# PROC010B_HD_Connector.net
KiCad netlist of a schematic drawn in Altium Designer
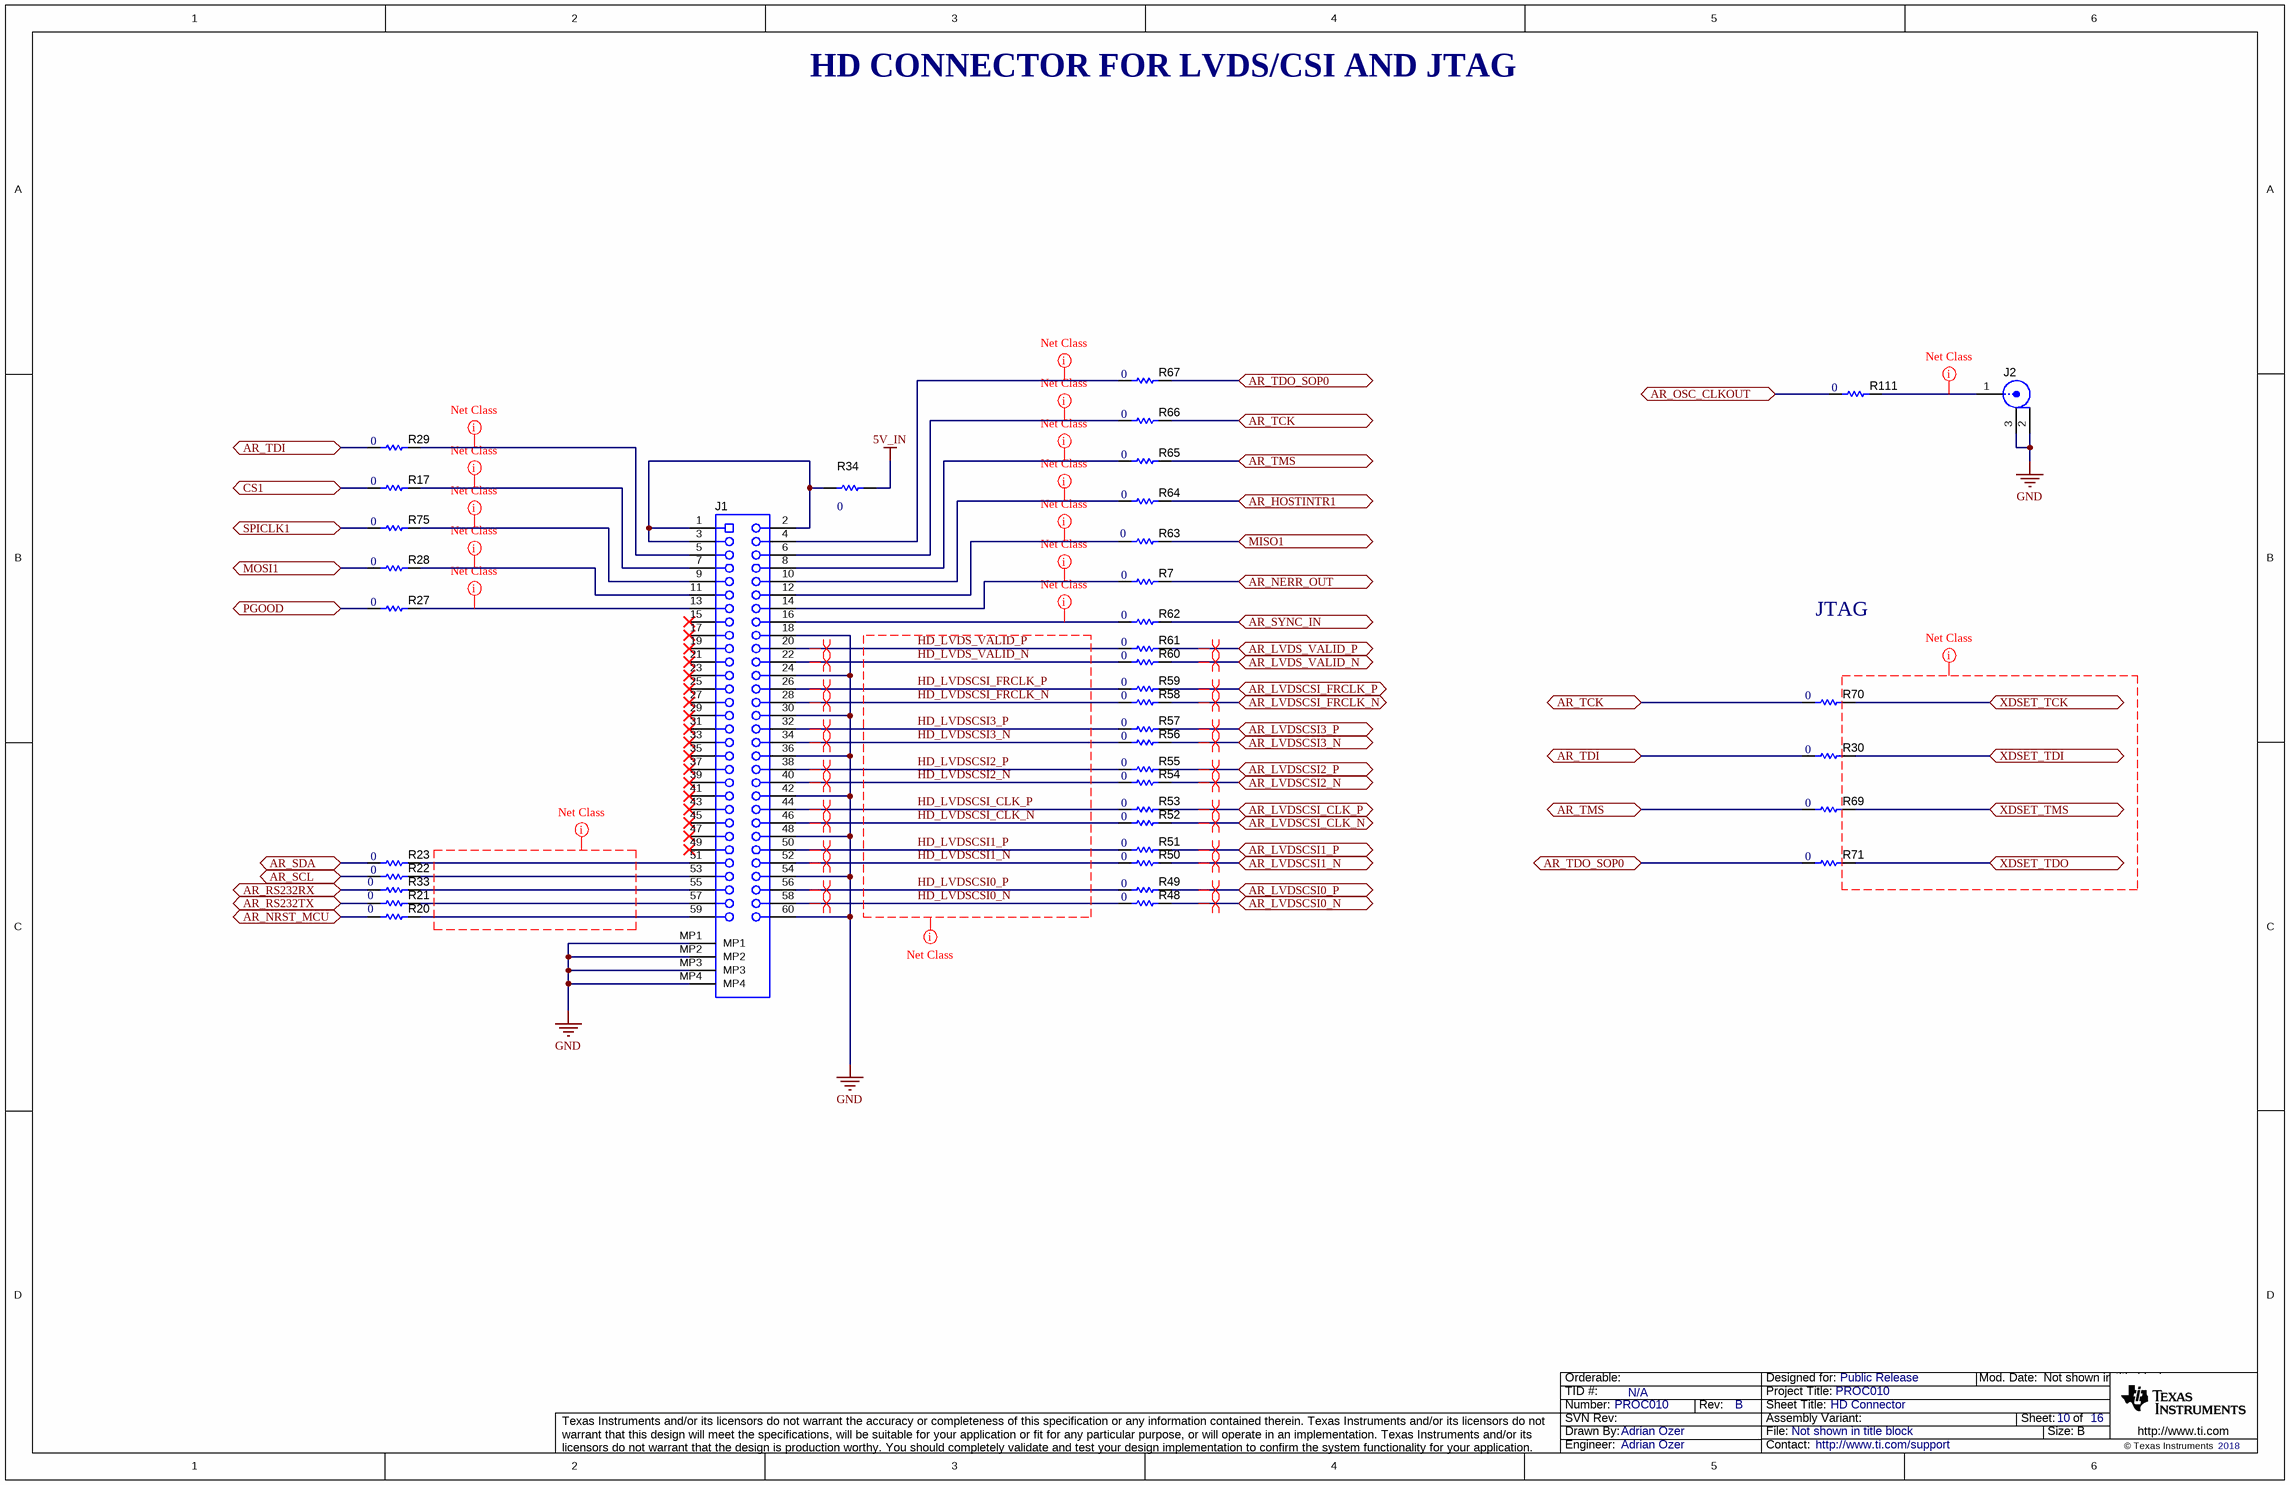
[diagram p0: PROC010B_HD Connector.SchDoc]

(export (version "E")
  (design (tool "Eeschema 10.0.6"))
  (components
    (comp (ref "J1")
      (value "QSH-030-01-L-D-A")
      (footprint "Samtec_QSH-030-01-X-D-A")
      (description "Receptacle, 0.5 mm, 30x2, Gold, TH")
      (fields (field (name "MANUFACTURER") "Samtec") (field (name "PUBLISHER") "Texas Instruments"))
      (libsource (lib "Altium Vault - TI") (part "Receptacle_30x2_4MP_LeftRight"))
    )
    (comp (ref "J2")
      (value "128-0711-201")
      (footprint "Johnson_128-0711-201")
      (description "UMC Straight Jack Receptacle, 50 Ohm, Gold, SMT")
      (fields
        (field (name "MANUFACTURER") "Cinch Connectivity")
        (field (name "PUBLISHER") "Texas Instruments")
      )
      (libsource (lib "Altium Vault - TI") (part "CMP-0055788-1"))
    )
    (comp (ref "R7")
      (value "CRCW02010000Z0ED")
      (footprint "0201_Silk")
      (description "RES, 0, 5%, 0.05 W, 0201")
      (fields (field (name "MANUFACTURER") "Vishay-Dale") (field (name "VALUEDISPLAYED") "0"))
      (libsource (lib "Altium Vault - TI") (part "Resistor"))
    )
    (comp (ref "R17")
      (value "CRCW02010000Z0ED")
      (footprint "0201_Silk")
      (description "RES, 0, 5%, 0.05 W, 0201")
      (fields (field (name "MANUFACTURER") "Vishay-Dale") (field (name "VALUEDISPLAYED") "0"))
      (libsource (lib "Altium Vault - TI") (part "Resistor"))
    )
    (comp (ref "R20")
      (value "CRCW02010000Z0ED")
      (footprint "0201_Silk")
      (description "RES, 0, 5%, 0.05 W, 0201")
      (fields (field (name "MANUFACTURER") "Vishay-Dale") (field (name "VALUEDISPLAYED") "0"))
      (libsource (lib "Altium Vault - TI") (part "Resistor"))
    )
    (comp (ref "R21")
      (value "CRCW02010000Z0ED")
      (footprint "0201_Silk")
      (description "RES, 0, 5%, 0.05 W, 0201")
      (fields (field (name "MANUFACTURER") "Vishay-Dale") (field (name "VALUEDISPLAYED") "0"))
      (libsource (lib "Altium Vault - TI") (part "Resistor"))
    )
    (comp (ref "R22")
      (value "CRCW02010000Z0ED")
      (footprint "0201_Silk")
      (description "RES, 0, 5%, 0.05 W, 0201")
      (fields (field (name "MANUFACTURER") "Vishay-Dale") (field (name "VALUEDISPLAYED") "0"))
      (libsource (lib "Altium Vault - TI") (part "Resistor"))
    )
    (comp (ref "R23")
      (value "CRCW02010000Z0ED")
      (footprint "0201_Silk")
      (description "RES, 0, 5%, 0.05 W, 0201")
      (fields (field (name "MANUFACTURER") "Vishay-Dale") (field (name "VALUEDISPLAYED") "0"))
      (libsource (lib "Altium Vault - TI") (part "Resistor"))
    )
    (comp (ref "R27")
      (value "CRCW02010000Z0ED")
      (footprint "0201_Silk")
      (description "RES, 0, 5%, 0.05 W, 0201")
      (fields (field (name "MANUFACTURER") "Vishay-Dale") (field (name "VALUEDISPLAYED") "0"))
      (libsource (lib "Altium Vault - TI") (part "Resistor"))
    )
    (comp (ref "R28")
      (value "CRCW02010000Z0ED")
      (footprint "0201_Silk")
      (description "RES, 0, 5%, 0.05 W, 0201")
      (fields (field (name "MANUFACTURER") "Vishay-Dale") (field (name "VALUEDISPLAYED") "0"))
      (libsource (lib "Altium Vault - TI") (part "Resistor"))
    )
    (comp (ref "R29")
      (value "CRCW02010000Z0ED")
      (footprint "0201_Silk")
      (description "RES, 0, 5%, 0.05 W, 0201")
      (fields (field (name "MANUFACTURER") "Vishay-Dale") (field (name "VALUEDISPLAYED") "0"))
      (libsource (lib "Altium Vault - TI") (part "Resistor"))
    )
    (comp (ref "R30")
      (value "CRCW02010000Z0ED")
      (footprint "0201_Silk")
      (description "RES, 0, 5%, 0.05 W, 0201")
      (fields (field (name "MANUFACTURER") "Vishay-Dale") (field (name "VALUEDISPLAYED") "0"))
      (libsource (lib "Altium Vault - TI") (part "Resistor"))
    )
    (comp (ref "R33")
      (value "CRCW02010000Z0ED")
      (footprint "0201_Silk")
      (description "RES, 0, 5%, 0.05 W, 0201")
      (fields (field (name "MANUFACTURER") "Vishay-Dale") (field (name "VALUEDISPLAYED") "0"))
      (libsource (lib "Altium Vault - TI") (part "Resistor"))
    )
    (comp (ref "R34")
      (value "CRCW20100000Z0EF")
      (footprint "2010L")
      (description "RES, 0, 5%, 0.75 W, AEC-Q200 Grade 0, 2010")
      (fields (field (name "MANUFACTURER") "Vishay-Dale") (field (name "VALUEDISPLAYED") "0"))
      (libsource (lib "Altium Vault - TI") (part "CMP-0016044-3"))
    )
    (comp (ref "R48")
      (value "CRCW02010000Z0ED")
      (footprint "0201_Silk")
      (description "RES, 0, 5%, 0.05 W, 0201")
      (fields (field (name "MANUFACTURER") "Vishay-Dale") (field (name "VALUEDISPLAYED") "0"))
      (libsource (lib "Altium Vault - TI") (part "Resistor"))
    )
    (comp (ref "R49")
      (value "CRCW02010000Z0ED")
      (footprint "0201_Silk")
      (description "RES, 0, 5%, 0.05 W, 0201")
      (fields (field (name "MANUFACTURER") "Vishay-Dale") (field (name "VALUEDISPLAYED") "0"))
      (libsource (lib "Altium Vault - TI") (part "Resistor"))
    )
    (comp (ref "R50")
      (value "CRCW02010000Z0ED")
      (footprint "0201_Silk")
      (description "RES, 0, 5%, 0.05 W, 0201")
      (fields (field (name "MANUFACTURER") "Vishay-Dale") (field (name "VALUEDISPLAYED") "0"))
      (libsource (lib "Altium Vault - TI") (part "Resistor"))
    )
    (comp (ref "R51")
      (value "CRCW02010000Z0ED")
      (footprint "0201_Silk")
      (description "RES, 0, 5%, 0.05 W, 0201")
      (fields (field (name "MANUFACTURER") "Vishay-Dale") (field (name "VALUEDISPLAYED") "0"))
      (libsource (lib "Altium Vault - TI") (part "Resistor"))
    )
    (comp (ref "R52")
      (value "CRCW02010000Z0ED")
      (footprint "0201_Silk")
      (description "RES, 0, 5%, 0.05 W, 0201")
      (fields (field (name "MANUFACTURER") "Vishay-Dale") (field (name "VALUEDISPLAYED") "0"))
      (libsource (lib "Altium Vault - TI") (part "Resistor"))
    )
    (comp (ref "R53")
      (value "CRCW02010000Z0ED")
      (footprint "0201_Silk")
      (description "RES, 0, 5%, 0.05 W, 0201")
      (fields (field (name "MANUFACTURER") "Vishay-Dale") (field (name "VALUEDISPLAYED") "0"))
      (libsource (lib "Altium Vault - TI") (part "Resistor"))
    )
    (comp (ref "R54")
      (value "CRCW02010000Z0ED")
      (footprint "0201_Silk")
      (description "RES, 0, 5%, 0.05 W, 0201")
      (fields (field (name "MANUFACTURER") "Vishay-Dale") (field (name "VALUEDISPLAYED") "0"))
      (libsource (lib "Altium Vault - TI") (part "Resistor"))
    )
    (comp (ref "R55")
      (value "CRCW02010000Z0ED")
      (footprint "0201_Silk")
      (description "RES, 0, 5%, 0.05 W, 0201")
      (fields (field (name "MANUFACTURER") "Vishay-Dale") (field (name "VALUEDISPLAYED") "0"))
      (libsource (lib "Altium Vault - TI") (part "Resistor"))
    )
    (comp (ref "R56")
      (value "CRCW02010000Z0ED")
      (footprint "0201_Silk")
      (description "RES, 0, 5%, 0.05 W, 0201")
      (fields (field (name "MANUFACTURER") "Vishay-Dale") (field (name "VALUEDISPLAYED") "0"))
      (libsource (lib "Altium Vault - TI") (part "Resistor"))
    )
    (comp (ref "R57")
      (value "CRCW02010000Z0ED")
      (footprint "0201_Silk")
      (description "RES, 0, 5%, 0.05 W, 0201")
      (fields (field (name "MANUFACTURER") "Vishay-Dale") (field (name "VALUEDISPLAYED") "0"))
      (libsource (lib "Altium Vault - TI") (part "Resistor"))
    )
    (comp (ref "R58")
      (value "CRCW02010000Z0ED")
      (footprint "0201_Silk")
      (description "RES, 0, 5%, 0.05 W, 0201")
      (fields (field (name "MANUFACTURER") "Vishay-Dale") (field (name "VALUEDISPLAYED") "0"))
      (libsource (lib "Altium Vault - TI") (part "Resistor"))
    )
    (comp (ref "R59")
      (value "CRCW02010000Z0ED")
      (footprint "0201_Silk")
      (description "RES, 0, 5%, 0.05 W, 0201")
      (fields (field (name "MANUFACTURER") "Vishay-Dale") (field (name "VALUEDISPLAYED") "0"))
      (libsource (lib "Altium Vault - TI") (part "Resistor"))
    )
    (comp (ref "R60")
      (value "CRCW02010000Z0ED")
      (footprint "0201_Silk")
      (description "RES, 0, 5%, 0.05 W, 0201")
      (fields (field (name "MANUFACTURER") "Vishay-Dale") (field (name "VALUEDISPLAYED") "0"))
      (libsource (lib "Altium Vault - TI") (part "Resistor"))
    )
    (comp (ref "R61")
      (value "CRCW02010000Z0ED")
      (footprint "0201_Silk")
      (description "RES, 0, 5%, 0.05 W, 0201")
      (fields (field (name "MANUFACTURER") "Vishay-Dale") (field (name "VALUEDISPLAYED") "0"))
      (libsource (lib "Altium Vault - TI") (part "Resistor"))
    )
    (comp (ref "R62")
      (value "CRCW02010000Z0ED")
      (footprint "0201_Silk")
      (description "RES, 0, 5%, 0.05 W, 0201")
      (fields (field (name "MANUFACTURER") "Vishay-Dale") (field (name "VALUEDISPLAYED") "0"))
      (libsource (lib "Altium Vault - TI") (part "Resistor"))
    )
    (comp (ref "R63")
      (value "CRCW02010000Z0ED")
      (footprint "0201_Silk")
      (description "RES, 0, 5%, 0.05 W, 0201")
      (fields (field (name "MANUFACTURER") "Vishay-Dale") (field (name "VALUEDISPLAYED") "0"))
      (libsource (lib "Altium Vault - TI") (part "Resistor"))
    )
    (comp (ref "R64")
      (value "CRCW02010000Z0ED")
      (footprint "0201_Silk")
      (description "RES, 0, 5%, 0.05 W, 0201")
      (fields (field (name "MANUFACTURER") "Vishay-Dale") (field (name "VALUEDISPLAYED") "0"))
      (libsource (lib "Altium Vault - TI") (part "Resistor"))
    )
    (comp (ref "R65")
      (value "CRCW02010000Z0ED")
      (footprint "0201_Silk")
      (description "RES, 0, 5%, 0.05 W, 0201")
      (fields (field (name "MANUFACTURER") "Vishay-Dale") (field (name "VALUEDISPLAYED") "0"))
      (libsource (lib "Altium Vault - TI") (part "Resistor"))
    )
    (comp (ref "R66")
      (value "CRCW02010000Z0ED")
      (footprint "0201_Silk")
      (description "RES, 0, 5%, 0.05 W, 0201")
      (fields (field (name "MANUFACTURER") "Vishay-Dale") (field (name "VALUEDISPLAYED") "0"))
      (libsource (lib "Altium Vault - TI") (part "Resistor"))
    )
    (comp (ref "R67")
      (value "CRCW02010000Z0ED")
      (footprint "0201_Silk")
      (description "RES, 0, 5%, 0.05 W, 0201")
      (fields (field (name "MANUFACTURER") "Vishay-Dale") (field (name "VALUEDISPLAYED") "0"))
      (libsource (lib "Altium Vault - TI") (part "Resistor"))
    )
    (comp (ref "R69")
      (value "CRCW02010000Z0ED")
      (footprint "0201_Silk")
      (description "RES, 0, 5%, 0.05 W, 0201")
      (fields (field (name "MANUFACTURER") "Vishay-Dale") (field (name "VALUEDISPLAYED") "0"))
      (libsource (lib "Altium Vault - TI") (part "Resistor"))
    )
    (comp (ref "R70")
      (value "CRCW02010000Z0ED")
      (footprint "0201_Silk")
      (description "RES, 0, 5%, 0.05 W, 0201")
      (fields (field (name "MANUFACTURER") "Vishay-Dale") (field (name "VALUEDISPLAYED") "0"))
      (libsource (lib "Altium Vault - TI") (part "Resistor"))
    )
    (comp (ref "R71")
      (value "CRCW02010000Z0ED")
      (footprint "0201_Silk")
      (description "RES, 0, 5%, 0.05 W, 0201")
      (fields (field (name "MANUFACTURER") "Vishay-Dale") (field (name "VALUEDISPLAYED") "0"))
      (libsource (lib "Altium Vault - TI") (part "Resistor"))
    )
    (comp (ref "R75")
      (value "CRCW02010000Z0ED")
      (footprint "0201_Silk")
      (description "RES, 0, 5%, 0.05 W, 0201")
      (fields (field (name "MANUFACTURER") "Vishay-Dale") (field (name "VALUEDISPLAYED") "0"))
      (libsource (lib "Altium Vault - TI") (part "Resistor"))
    )
    (comp (ref "R111")
      (value "CRCW02010000Z0ED")
      (footprint "0201_Silk")
      (description "RES, 0, 5%, 0.05 W, 0201")
      (fields (field (name "MANUFACTURER") "Vishay-Dale") (field (name "VALUEDISPLAYED") "0"))
      (libsource (lib "Altium Vault - TI") (part "Resistor"))
    )
  )
  (nets
    (net (code "1") (name "/AR_HOSTINTR1") (class "Default")
      (node (ref "R64") (pin "2") (pinfunction "2_2") (pintype "passive"))
    )
    (net (code "2") (name "/AR_LVDSCSI0_N") (class "Default")
      (node (ref "R48") (pin "2") (pinfunction "2_2") (pintype "passive"))
    )
    (net (code "3") (name "/AR_LVDSCSI0_P") (class "Default")
      (node (ref "R49") (pin "2") (pinfunction "2_2") (pintype "passive"))
    )
    (net (code "4") (name "/AR_LVDSCSI1_N") (class "Default")
      (node (ref "R50") (pin "2") (pinfunction "2_2") (pintype "passive"))
    )
    (net (code "5") (name "/AR_LVDSCSI1_P") (class "Default")
      (node (ref "R51") (pin "2") (pinfunction "2_2") (pintype "passive"))
    )
    (net (code "6") (name "/AR_LVDSCSI2_N") (class "Default")
      (node (ref "R54") (pin "2") (pinfunction "2_2") (pintype "passive"))
    )
    (net (code "7") (name "/AR_LVDSCSI2_P") (class "Default")
      (node (ref "R55") (pin "2") (pinfunction "2_2") (pintype "passive"))
    )
    (net (code "8") (name "/AR_LVDSCSI3_N") (class "Default")
      (node (ref "R56") (pin "2") (pinfunction "2_2") (pintype "passive"))
    )
    (net (code "9") (name "/AR_LVDSCSI3_P") (class "Default")
      (node (ref "R57") (pin "2") (pinfunction "2_2") (pintype "passive"))
    )
    (net (code "10") (name "/AR_LVDSCSI_CLK_N") (class "Default")
      (node (ref "R52") (pin "2") (pinfunction "2_2") (pintype "passive"))
    )
    (net (code "11") (name "/AR_LVDSCSI_CLK_P") (class "Default")
      (node (ref "R53") (pin "2") (pinfunction "2_2") (pintype "passive"))
    )
    (net (code "12") (name "/AR_LVDSCSI_FRCLK_N") (class "Default")
      (node (ref "R58") (pin "2") (pinfunction "2_2") (pintype "passive"))
    )
    (net (code "13") (name "/AR_LVDSCSI_FRCLK_P") (class "Default")
      (node (ref "R59") (pin "2") (pinfunction "2_2") (pintype "passive"))
    )
    (net (code "14") (name "/AR_LVDS_VALID_N") (class "Default")
      (node (ref "R60") (pin "2") (pinfunction "2_2") (pintype "passive"))
    )
    (net (code "15") (name "/AR_LVDS_VALID_P") (class "Default")
      (node (ref "R61") (pin "2") (pinfunction "2_2") (pintype "passive"))
    )
    (net (code "16") (name "/AR_NERR_OUT") (class "Default")
      (node (ref "R7") (pin "2") (pinfunction "2_2") (pintype "passive"))
    )
    (net (code "17") (name "/AR_NRST_MCU") (class "Default")
      (node (ref "R20") (pin "1") (pinfunction "1_1") (pintype "passive"))
    )
    (net (code "18") (name "/AR_OSC_CLKOUT") (class "Default")
      (node (ref "R111") (pin "1") (pinfunction "1_1") (pintype "passive"))
    )
    (net (code "19") (name "/AR_RS232RX") (class "Default")
      (node (ref "R33") (pin "1") (pinfunction "1_1") (pintype "passive"))
    )
    (net (code "20") (name "/AR_RS232TX") (class "Default")
      (node (ref "R21") (pin "1") (pinfunction "1_1") (pintype "passive"))
    )
    (net (code "21") (name "/AR_SCL") (class "Default")
      (node (ref "R22") (pin "1") (pinfunction "1_1") (pintype "passive"))
    )
    (net (code "22") (name "/AR_SDA") (class "Default")
      (node (ref "R23") (pin "1") (pinfunction "1_1") (pintype "passive"))
    )
    (net (code "23") (name "/AR_SYNC_IN") (class "Default")
      (node (ref "R62") (pin "2") (pinfunction "2_2") (pintype "passive"))
    )
    (net (code "24") (name "/AR_TCK") (class "Default")
      (node (ref "R66") (pin "2") (pinfunction "2_2") (pintype "passive"))
      (node (ref "R70") (pin "1") (pinfunction "1_1") (pintype "passive"))
    )
    (net (code "25") (name "/AR_TDI") (class "Default")
      (node (ref "R29") (pin "1") (pinfunction "1_1") (pintype "passive"))
      (node (ref "R30") (pin "1") (pinfunction "1_1") (pintype "passive"))
    )
    (net (code "26") (name "/AR_TDO_SOP0") (class "Default")
      (node (ref "R67") (pin "2") (pinfunction "2_2") (pintype "passive"))
      (node (ref "R71") (pin "1") (pinfunction "1_1") (pintype "passive"))
    )
    (net (code "27") (name "/AR_TMS") (class "Default")
      (node (ref "R65") (pin "2") (pinfunction "2_2") (pintype "passive"))
      (node (ref "R69") (pin "1") (pinfunction "1_1") (pintype "passive"))
    )
    (net (code "28") (name "/CS1") (class "Default")
      (node (ref "R17") (pin "1") (pinfunction "1_1") (pintype "passive"))
    )
    (net (code "29") (name "/HD_LVDSCSI0_N") (class "Default")
      (node (ref "J1") (pin "58") (pinfunction "58_58") (pintype "passive"))
      (node (ref "R48") (pin "1") (pinfunction "1_1") (pintype "passive"))
    )
    (net (code "30") (name "/HD_LVDSCSI0_P") (class "Default")
      (node (ref "J1") (pin "56") (pinfunction "56_56") (pintype "passive"))
      (node (ref "R49") (pin "1") (pinfunction "1_1") (pintype "passive"))
    )
    (net (code "31") (name "/HD_LVDSCSI1_N") (class "Default")
      (node (ref "J1") (pin "52") (pinfunction "52_52") (pintype "passive"))
      (node (ref "R50") (pin "1") (pinfunction "1_1") (pintype "passive"))
    )
    (net (code "32") (name "/HD_LVDSCSI1_P") (class "Default")
      (node (ref "J1") (pin "50") (pinfunction "50_50") (pintype "passive"))
      (node (ref "R51") (pin "1") (pinfunction "1_1") (pintype "passive"))
    )
    (net (code "33") (name "/HD_LVDSCSI2_N") (class "Default")
      (node (ref "J1") (pin "40") (pinfunction "40_40") (pintype "passive"))
      (node (ref "R54") (pin "1") (pinfunction "1_1") (pintype "passive"))
    )
    (net (code "34") (name "/HD_LVDSCSI2_P") (class "Default")
      (node (ref "J1") (pin "38") (pinfunction "38_38") (pintype "passive"))
      (node (ref "R55") (pin "1") (pinfunction "1_1") (pintype "passive"))
    )
    (net (code "35") (name "/HD_LVDSCSI3_N") (class "Default")
      (node (ref "J1") (pin "34") (pinfunction "34_34") (pintype "passive"))
      (node (ref "R56") (pin "1") (pinfunction "1_1") (pintype "passive"))
    )
    (net (code "36") (name "/HD_LVDSCSI3_P") (class "Default")
      (node (ref "J1") (pin "32") (pinfunction "32_32") (pintype "passive"))
      (node (ref "R57") (pin "1") (pinfunction "1_1") (pintype "passive"))
    )
    (net (code "37") (name "/HD_LVDSCSI_CLK_N") (class "Default")
      (node (ref "J1") (pin "46") (pinfunction "46_46") (pintype "passive"))
      (node (ref "R52") (pin "1") (pinfunction "1_1") (pintype "passive"))
    )
    (net (code "38") (name "/HD_LVDSCSI_CLK_P") (class "Default")
      (node (ref "J1") (pin "44") (pinfunction "44_44") (pintype "passive"))
      (node (ref "R53") (pin "1") (pinfunction "1_1") (pintype "passive"))
    )
    (net (code "39") (name "/HD_LVDSCSI_FRCLK_N") (class "Default")
      (node (ref "J1") (pin "28") (pinfunction "28_28") (pintype "passive"))
      (node (ref "R58") (pin "1") (pinfunction "1_1") (pintype "passive"))
    )
    (net (code "40") (name "/HD_LVDSCSI_FRCLK_P") (class "Default")
      (node (ref "J1") (pin "26") (pinfunction "26_26") (pintype "passive"))
      (node (ref "R59") (pin "1") (pinfunction "1_1") (pintype "passive"))
    )
    (net (code "41") (name "/HD_LVDS_VALID_N") (class "Default")
      (node (ref "J1") (pin "22") (pinfunction "22_22") (pintype "passive"))
      (node (ref "R60") (pin "1") (pinfunction "1_1") (pintype "passive"))
    )
    (net (code "42") (name "/HD_LVDS_VALID_P") (class "Default")
      (node (ref "J1") (pin "20") (pinfunction "20_20") (pintype "passive"))
      (node (ref "R61") (pin "1") (pinfunction "1_1") (pintype "passive"))
    )
    (net (code "43") (name "/MISO1") (class "Default")
      (node (ref "R63") (pin "2") (pinfunction "2_2") (pintype "passive"))
    )
    (net (code "44") (name "/MOSI1") (class "Default")
      (node (ref "R28") (pin "1") (pinfunction "1_1") (pintype "passive"))
    )
    (net (code "45") (name "/PGOOD") (class "Default")
      (node (ref "R27") (pin "1") (pinfunction "1_1") (pintype "passive"))
    )
    (net (code "46") (name "/SPICLK1") (class "Default")
      (node (ref "R75") (pin "1") (pinfunction "1_1") (pintype "passive"))
    )
    (net (code "47") (name "/XDSET_TCK") (class "Default")
      (node (ref "R70") (pin "2") (pinfunction "2_2") (pintype "passive"))
    )
    (net (code "48") (name "/XDSET_TDI") (class "Default")
      (node (ref "R30") (pin "2") (pinfunction "2_2") (pintype "passive"))
    )
    (net (code "49") (name "/XDSET_TDO") (class "Default")
      (node (ref "R71") (pin "2") (pinfunction "2_2") (pintype "passive"))
    )
    (net (code "50") (name "/XDSET_TMS") (class "Default")
      (node (ref "R69") (pin "2") (pinfunction "2_2") (pintype "passive"))
    )
    (net (code "51") (name "5V_IN") (class "Default")
      (node (ref "R34") (pin "2") (pinfunction "2_2") (pintype "passive"))
    )
    (net (code "52") (name "GND") (class "Default")
      (node (ref "J1") (pin "18") (pinfunction "18_18") (pintype "passive"))
      (node (ref "J1") (pin "24") (pinfunction "24_24") (pintype "passive"))
      (node (ref "J1") (pin "30") (pinfunction "30_30") (pintype "passive"))
      (node (ref "J1") (pin "36") (pinfunction "36_36") (pintype "passive"))
      (node (ref "J1") (pin "42") (pinfunction "42_42") (pintype "passive"))
      (node (ref "J1") (pin "48") (pinfunction "48_48") (pintype "passive"))
      (node (ref "J1") (pin "54") (pinfunction "54_54") (pintype "passive"))
      (node (ref "J1") (pin "60") (pinfunction "60_60") (pintype "passive"))
      (node (ref "J1") (pin "MP1") (pinfunction "MP1_MP1") (pintype "passive"))
      (node (ref "J1") (pin "MP2") (pinfunction "MP2_MP2") (pintype "passive"))
      (node (ref "J1") (pin "MP3") (pinfunction "MP3_MP3") (pintype "passive"))
      (node (ref "J1") (pin "MP4") (pinfunction "MP4_MP4") (pintype "passive"))
      (node (ref "J2") (pin "2") (pinfunction "2_2") (pintype "passive"))
      (node (ref "J2") (pin "3") (pinfunction "3_3") (pintype "passive"))
    )
    (net (code "53") (name "Net-(J1-Pad1)") (class "Default")
      (node (ref "J1") (pin "1") (pinfunction "1_1") (pintype "passive"))
      (node (ref "J1") (pin "2") (pinfunction "2_2") (pintype "passive"))
      (node (ref "J1") (pin "3") (pinfunction "3_3") (pintype "passive"))
      (node (ref "R34") (pin "1") (pinfunction "1_1") (pintype "passive"))
    )
    (net (code "54") (name "Net-(J1-Pad4)") (class "Default")
      (node (ref "J1") (pin "4") (pinfunction "4_4") (pintype "passive"))
      (node (ref "R67") (pin "1") (pinfunction "1_1") (pintype "passive"))
    )
    (net (code "55") (name "Net-(J1-Pad5)") (class "Default")
      (node (ref "J1") (pin "5") (pinfunction "5_5") (pintype "passive"))
      (node (ref "R29") (pin "2") (pinfunction "2_2") (pintype "passive"))
    )
    (net (code "56") (name "Net-(J1-Pad6)") (class "Default")
      (node (ref "J1") (pin "6") (pinfunction "6_6") (pintype "passive"))
      (node (ref "R66") (pin "1") (pinfunction "1_1") (pintype "passive"))
    )
    (net (code "57") (name "Net-(J1-Pad7)") (class "Default")
      (node (ref "J1") (pin "7") (pinfunction "7_7") (pintype "passive"))
      (node (ref "R17") (pin "2") (pinfunction "2_2") (pintype "passive"))
    )
    (net (code "58") (name "Net-(J1-Pad8)") (class "Default")
      (node (ref "J1") (pin "8") (pinfunction "8_8") (pintype "passive"))
      (node (ref "R65") (pin "1") (pinfunction "1_1") (pintype "passive"))
    )
    (net (code "59") (name "Net-(J1-Pad9)") (class "Default")
      (node (ref "J1") (pin "9") (pinfunction "9_9") (pintype "passive"))
      (node (ref "R75") (pin "2") (pinfunction "2_2") (pintype "passive"))
    )
    (net (code "60") (name "Net-(J1-Pad10)") (class "Default")
      (node (ref "J1") (pin "10") (pinfunction "10_10") (pintype "passive"))
      (node (ref "R64") (pin "1") (pinfunction "1_1") (pintype "passive"))
    )
    (net (code "61") (name "Net-(J1-Pad11)") (class "Default")
      (node (ref "J1") (pin "11") (pinfunction "11_11") (pintype "passive"))
      (node (ref "R28") (pin "2") (pinfunction "2_2") (pintype "passive"))
    )
    (net (code "62") (name "Net-(J1-Pad12)") (class "Default")
      (node (ref "J1") (pin "12") (pinfunction "12_12") (pintype "passive"))
      (node (ref "R63") (pin "1") (pinfunction "1_1") (pintype "passive"))
    )
    (net (code "63") (name "Net-(J1-Pad13)") (class "Default")
      (node (ref "J1") (pin "13") (pinfunction "13_13") (pintype "passive"))
      (node (ref "R27") (pin "2") (pinfunction "2_2") (pintype "passive"))
    )
    (net (code "64") (name "Net-(J1-Pad14)") (class "Default")
      (node (ref "J1") (pin "14") (pinfunction "14_14") (pintype "passive"))
      (node (ref "R7") (pin "1") (pinfunction "1_1") (pintype "passive"))
    )
    (net (code "65") (name "Net-(J1-Pad16)") (class "Default")
      (node (ref "J1") (pin "16") (pinfunction "16_16") (pintype "passive"))
      (node (ref "R62") (pin "1") (pinfunction "1_1") (pintype "passive"))
    )
    (net (code "66") (name "Net-(J1-Pad51)") (class "Default")
      (node (ref "J1") (pin "51") (pinfunction "51_51") (pintype "passive"))
      (node (ref "R23") (pin "2") (pinfunction "2_2") (pintype "passive"))
    )
    (net (code "67") (name "Net-(J1-Pad53)") (class "Default")
      (node (ref "J1") (pin "53") (pinfunction "53_53") (pintype "passive"))
      (node (ref "R22") (pin "2") (pinfunction "2_2") (pintype "passive"))
    )
    (net (code "68") (name "Net-(J1-Pad55)") (class "Default")
      (node (ref "J1") (pin "55") (pinfunction "55_55") (pintype "passive"))
      (node (ref "R33") (pin "2") (pinfunction "2_2") (pintype "passive"))
    )
    (net (code "69") (name "Net-(J1-Pad57)") (class "Default")
      (node (ref "J1") (pin "57") (pinfunction "57_57") (pintype "passive"))
      (node (ref "R21") (pin "2") (pinfunction "2_2") (pintype "passive"))
    )
    (net (code "70") (name "Net-(J1-Pad59)") (class "Default")
      (node (ref "J1") (pin "59") (pinfunction "59_59") (pintype "passive"))
      (node (ref "R20") (pin "2") (pinfunction "2_2") (pintype "passive"))
    )
    (net (code "71") (name "Net-(J2-Pad1)") (class "Default")
      (node (ref "J2") (pin "1") (pinfunction "1_1") (pintype "passive"))
      (node (ref "R111") (pin "2") (pinfunction "2_2") (pintype "passive"))
    )
    (net (code "72") (name "unconnected-(J1-Pad15)") (class "Default")
      (node (ref "J1") (pin "15") (pinfunction "15_15") (pintype "passive+no_connect"))
    )
    (net (code "73") (name "unconnected-(J1-Pad17)") (class "Default")
      (node (ref "J1") (pin "17") (pinfunction "17_17") (pintype "passive+no_connect"))
    )
    (net (code "74") (name "unconnected-(J1-Pad19)") (class "Default")
      (node (ref "J1") (pin "19") (pinfunction "19_19") (pintype "passive+no_connect"))
    )
    (net (code "75") (name "unconnected-(J1-Pad21)") (class "Default")
      (node (ref "J1") (pin "21") (pinfunction "21_21") (pintype "passive+no_connect"))
    )
    (net (code "76") (name "unconnected-(J1-Pad23)") (class "Default")
      (node (ref "J1") (pin "23") (pinfunction "23_23") (pintype "passive+no_connect"))
    )
    (net (code "77") (name "unconnected-(J1-Pad25)") (class "Default")
      (node (ref "J1") (pin "25") (pinfunction "25_25") (pintype "passive+no_connect"))
    )
    (net (code "78") (name "unconnected-(J1-Pad27)") (class "Default")
      (node (ref "J1") (pin "27") (pinfunction "27_27") (pintype "passive+no_connect"))
    )
    (net (code "79") (name "unconnected-(J1-Pad29)") (class "Default")
      (node (ref "J1") (pin "29") (pinfunction "29_29") (pintype "passive+no_connect"))
    )
    (net (code "80") (name "unconnected-(J1-Pad31)") (class "Default")
      (node (ref "J1") (pin "31") (pinfunction "31_31") (pintype "passive+no_connect"))
    )
    (net (code "81") (name "unconnected-(J1-Pad33)") (class "Default")
      (node (ref "J1") (pin "33") (pinfunction "33_33") (pintype "passive+no_connect"))
    )
    (net (code "82") (name "unconnected-(J1-Pad35)") (class "Default")
      (node (ref "J1") (pin "35") (pinfunction "35_35") (pintype "passive+no_connect"))
    )
    (net (code "83") (name "unconnected-(J1-Pad37)") (class "Default")
      (node (ref "J1") (pin "37") (pinfunction "37_37") (pintype "passive+no_connect"))
    )
    (net (code "84") (name "unconnected-(J1-Pad39)") (class "Default")
      (node (ref "J1") (pin "39") (pinfunction "39_39") (pintype "passive+no_connect"))
    )
    (net (code "85") (name "unconnected-(J1-Pad41)") (class "Default")
      (node (ref "J1") (pin "41") (pinfunction "41_41") (pintype "passive+no_connect"))
    )
    (net (code "86") (name "unconnected-(J1-Pad43)") (class "Default")
      (node (ref "J1") (pin "43") (pinfunction "43_43") (pintype "passive+no_connect"))
    )
    (net (code "87") (name "unconnected-(J1-Pad45)") (class "Default")
      (node (ref "J1") (pin "45") (pinfunction "45_45") (pintype "passive+no_connect"))
    )
    (net (code "88") (name "unconnected-(J1-Pad47)") (class "Default")
      (node (ref "J1") (pin "47") (pinfunction "47_47") (pintype "passive+no_connect"))
    )
    (net (code "89") (name "unconnected-(J1-Pad49)") (class "Default")
      (node (ref "J1") (pin "49") (pinfunction "49_49") (pintype "passive+no_connect"))
    )
  )
)
